# GWLSensorv6.net
KiCad netlist of a schematic drawn in EAGLE
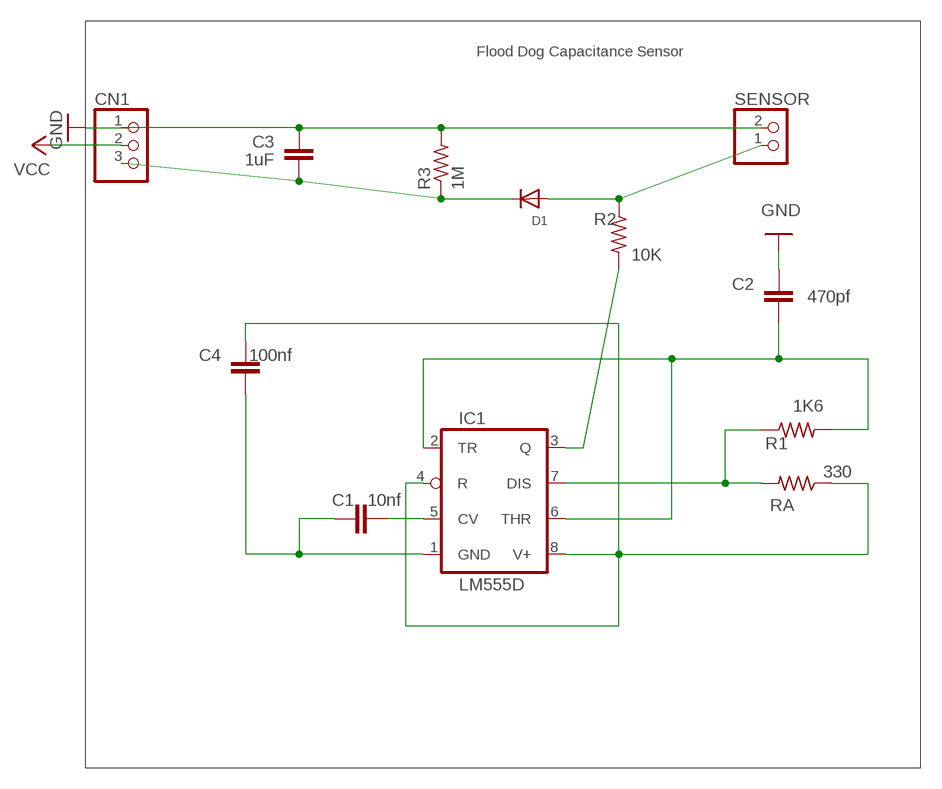
[diagram p0: schematic, sheet 1]

(export (version "E")
  (design (tool "Eeschema 10.0.6"))
  (components
    (comp (ref "C1")
      (value "10nf")
      (footprint "eagle-import:C0805")
      (libsource (lib "eagle-import") (part "C-EUC0805"))
    )
    (comp (ref "C2")
      (value "470pf")
      (footprint "eagle-import:C0805")
      (libsource (lib "eagle-import") (part "C-EUC0805"))
    )
    (comp (ref "C3")
      (value "1uF")
      (footprint "eagle-import:C0805")
      (libsource (lib "eagle-import") (part "C-EUC0805"))
    )
    (comp (ref "C4")
      (value "100nf")
      (footprint "eagle-import:C0805")
      (libsource (lib "eagle-import") (part "C-EUC0805"))
    )
    (comp (ref "CN1")
      (value "JST_3PIN")
      (footprint "eagle-import:JSTPH3")
      (libsource (lib "eagle-import") (part "JST_3PIN"))
    )
    (comp (ref "D1")
      (value "DIODESMA")
      (footprint "eagle-import:SMADIODE")
      (libsource (lib "eagle-import") (part "DIODESMA"))
    )
    (comp (ref "IC1")
      (value "LM555D")
      (footprint "eagle-import:SO08")
      (libsource (lib "eagle-import") (part "555DLM"))
    )
    (comp (ref "R1")
      (value "1K6")
      (footprint "eagle-import:R0805")
      (libsource (lib "eagle-import") (part "R-US_R0805"))
    )
    (comp (ref "R2")
      (value "10K")
      (footprint "eagle-import:R0805")
      (libsource (lib "eagle-import") (part "R-US_R0805"))
    )
    (comp (ref "R3")
      (value "1M")
      (footprint "eagle-import:R0805")
      (libsource (lib "eagle-import") (part "R-US_R0805"))
    )
    (comp (ref "RA")
      (value "330")
      (footprint "eagle-import:R0805")
      (libsource (lib "eagle-import") (part "R-US_R0805"))
    )
    (comp (ref "SENSOR")
      (value "JST_2PIN-SMT")
      (footprint "eagle-import:JST-PH-2-SMT")
      (libsource (lib "eagle-import") (part "JST_2PIN-SMT"))
    )
  )
  (nets
    (net (code "1") (name "GND") (class "Default")
      (node (ref "C2") (pin "2") (pinfunction "2_2") (pintype "passive"))
      (node (ref "C3") (pin "2") (pinfunction "2_2") (pintype "passive"))
      (node (ref "CN1") (pin "1") (pinfunction "1_1") (pintype "passive"))
      (node (ref "R3") (pin "2") (pinfunction "2_2") (pintype "passive"))
      (node (ref "SENSOR") (pin "2") (pinfunction "1_2") (pintype "passive"))
    )
    (net (code "2") (name "Net-(C3-Pad1)") (class "Default")
      (node (ref "C3") (pin "1") (pinfunction "1_1") (pintype "passive"))
      (node (ref "CN1") (pin "3") (pinfunction "3_3") (pintype "passive"))
      (node (ref "D1") (pin "C") (pinfunction "C_C") (pintype "passive"))
      (node (ref "R3") (pin "1") (pinfunction "1_1") (pintype "passive"))
    )
    (net (code "3") (name "Net-(IC1-CV)") (class "Default")
      (node (ref "C1") (pin "2") (pinfunction "2_2") (pintype "passive"))
      (node (ref "IC1") (pin "5") (pinfunction "CV_5") (pintype "input"))
    )
    (net (code "4") (name "Net-(IC1-DIS)") (class "Default")
      (node (ref "IC1") (pin "7") (pinfunction "DIS_7") (pintype "input"))
      (node (ref "R1") (pin "1") (pinfunction "1_1") (pintype "passive"))
      (node (ref "RA") (pin "2") (pinfunction "2_2") (pintype "passive"))
    )
    (net (code "5") (name "Net-(IC1-GND)") (class "Default")
      (node (ref "C1") (pin "1") (pinfunction "1_1") (pintype "passive"))
      (node (ref "C4") (pin "1") (pinfunction "1_1") (pintype "passive"))
      (node (ref "IC1") (pin "1") (pinfunction "GND_1") (pintype "power_in"))
    )
    (net (code "6") (name "Net-(IC1-Q)") (class "Default")
      (node (ref "IC1") (pin "3") (pinfunction "Q_3") (pintype "output"))
      (node (ref "R2") (pin "2") (pinfunction "2_2") (pintype "passive"))
    )
    (net (code "7") (name "Net-(IC1-R)") (class "Default")
      (node (ref "C4") (pin "2") (pinfunction "2_2") (pintype "passive"))
      (node (ref "IC1") (pin "4") (pinfunction "R_4") (pintype "input"))
      (node (ref "IC1") (pin "8") (pinfunction "V+_8") (pintype "power_in"))
      (node (ref "RA") (pin "1") (pinfunction "1_1") (pintype "passive"))
    )
    (net (code "8") (name "Net-(IC1-THR)") (class "Default")
      (node (ref "C2") (pin "1") (pinfunction "1_1") (pintype "passive"))
      (node (ref "IC1") (pin "2") (pinfunction "TR_2") (pintype "input"))
      (node (ref "IC1") (pin "6") (pinfunction "THR_6") (pintype "input"))
      (node (ref "R1") (pin "2") (pinfunction "2_2") (pintype "passive"))
    )
    (net (code "9") (name "Net-(SENSOR-2)") (class "Default")
      (node (ref "D1") (pin "A") (pinfunction "A_A") (pintype "passive"))
      (node (ref "R2") (pin "1") (pinfunction "1_1") (pintype "passive"))
      (node (ref "SENSOR") (pin "1") (pinfunction "2_1") (pintype "passive"))
    )
    (net (code "10") (name "VCC") (class "Default")
      (node (ref "CN1") (pin "2") (pinfunction "2_2") (pintype "passive"))
    )
  )
)
